# MODUL_GNU-PI_BRIDGE_V100.net
KiCad netlist of a schematic drawn in EAGLE
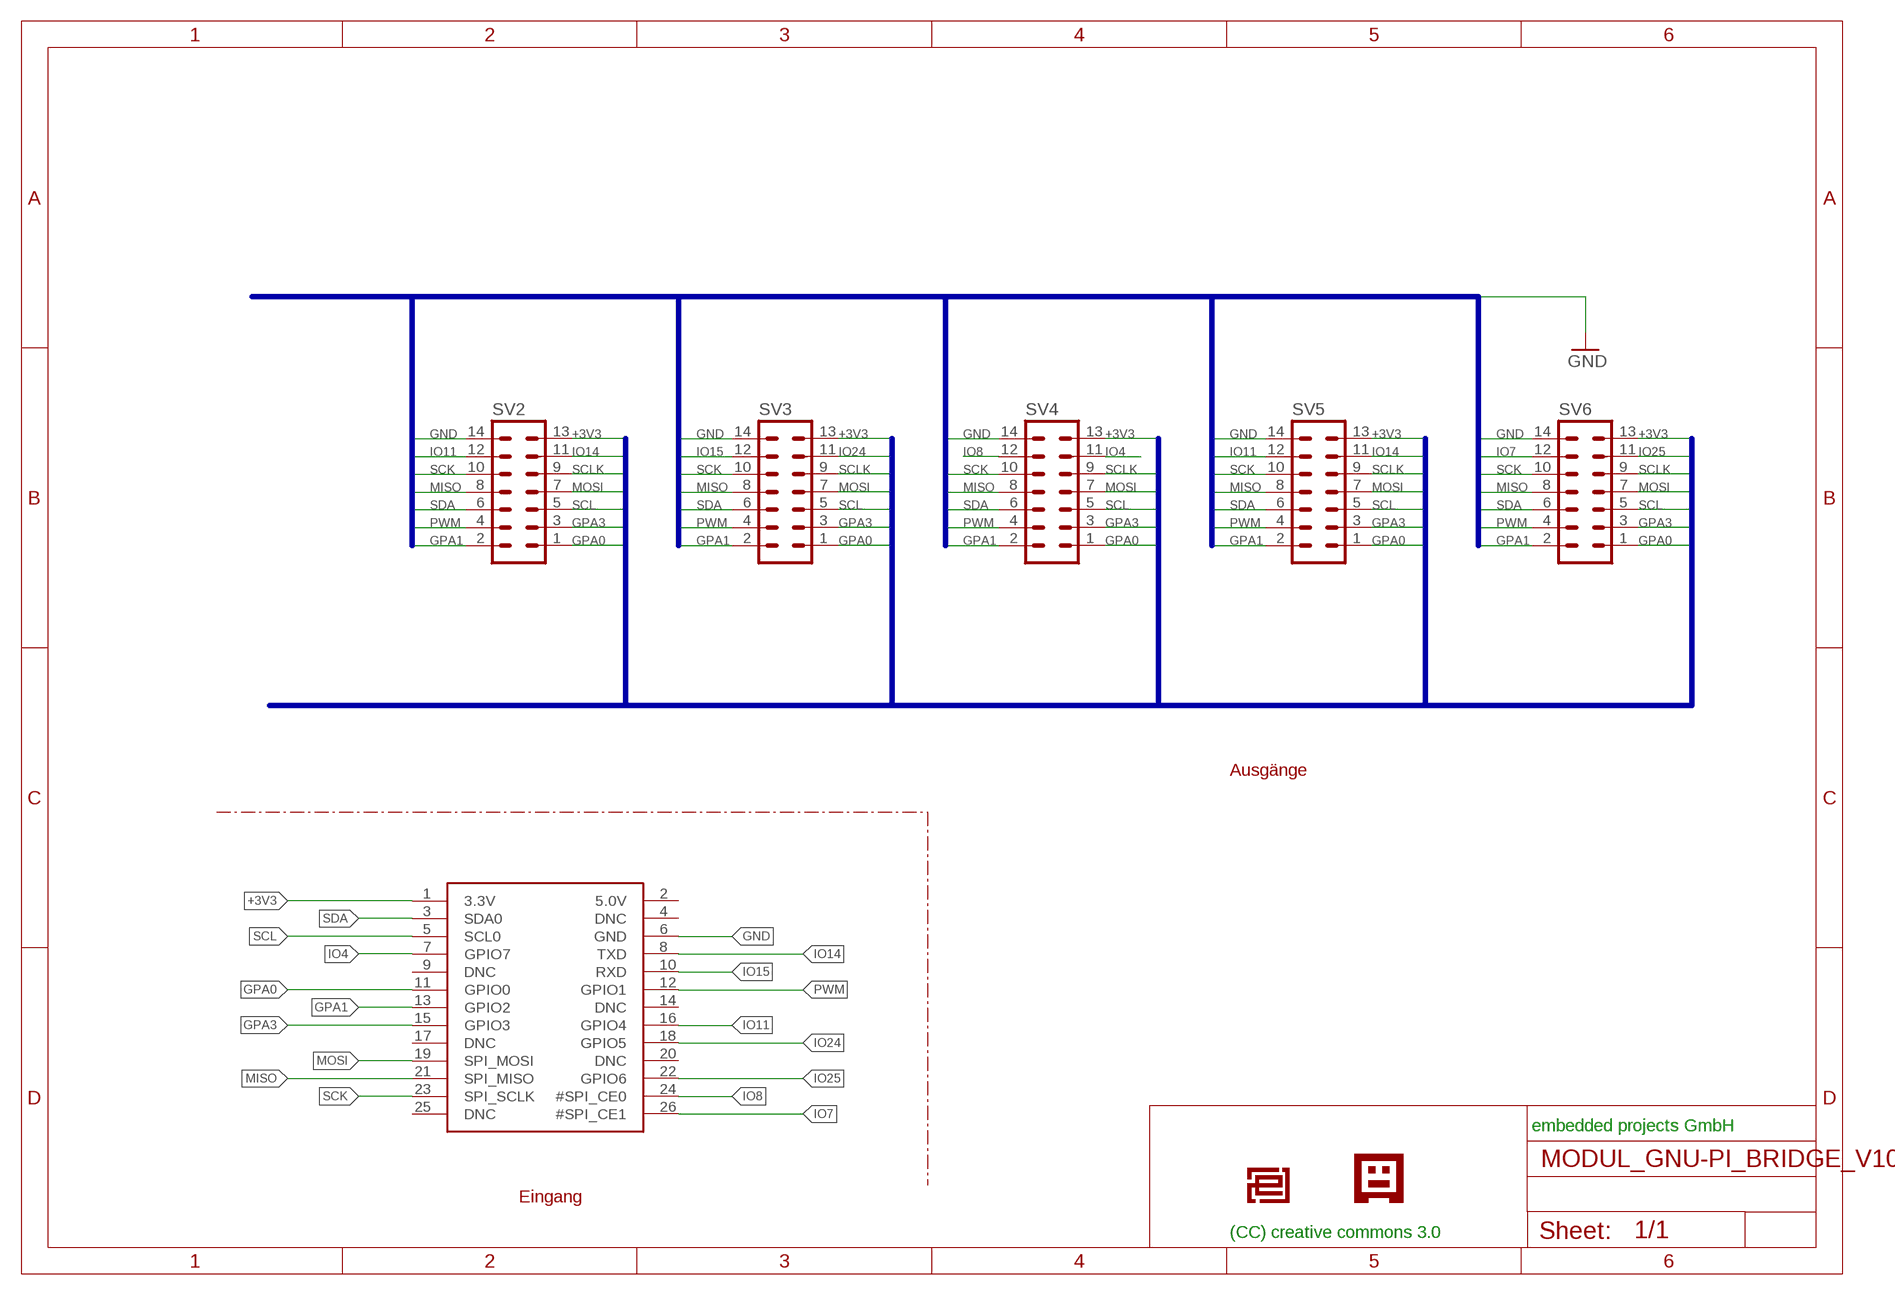
[diagram p0: schematic, sheet 1]

(export (version "E")
  (design (tool "Eeschema 10.0.6"))
  (components
    (comp (ref "SV2")
      (value "ML14")
      (footprint "eagle-import:ML14")
      (libsource (lib "eagle-import") (part "ML14"))
    )
    (comp (ref "SV3")
      (value "ML14")
      (footprint "eagle-import:ML14")
      (libsource (lib "eagle-import") (part "ML14"))
    )
    (comp (ref "SV4")
      (value "ML14")
      (footprint "eagle-import:ML14")
      (libsource (lib "eagle-import") (part "ML14"))
    )
    (comp (ref "SV5")
      (value "ML14")
      (footprint "eagle-import:ML14")
      (libsource (lib "eagle-import") (part "ML14"))
    )
    (comp (ref "SV6")
      (value "ML14")
      (footprint "eagle-import:ML14")
      (libsource (lib "eagle-import") (part "ML14"))
    )
    (comp (ref "U$1")
      (value "RASPBERRYPI_BB")
      (footprint "eagle-import:RASBERRYPI_SHIELD")
      (libsource (lib "eagle-import") (part "RASPBERRYPI_BB"))
    )
    (comp (ref "U$2")
      (value "EPLOGOSIEB")
      (footprint "eagle-import:EPLOGOSIEBDRUCK")
      (libsource (lib "eagle-import") (part "EPLOGOSIEB"))
    )
    (comp (ref "U$4")
      (value "GNUBLINLOGOSIEB")
      (footprint "eagle-import:GNUSIEBDRUCK")
      (libsource (lib "eagle-import") (part "GNUBLINLOGOSIEB"))
    )
  )
  (nets
    (net (code "1") (name "+3V3") (class "Default")
      (node (ref "SV2") (pin "13") (pinfunction "13_13") (pintype "passive"))
      (node (ref "SV3") (pin "13") (pinfunction "13_13") (pintype "passive"))
      (node (ref "SV4") (pin "13") (pinfunction "13_13") (pintype "passive"))
      (node (ref "SV5") (pin "13") (pinfunction "13_13") (pintype "passive"))
      (node (ref "SV6") (pin "13") (pinfunction "13_13") (pintype "passive"))
      (node (ref "U$1") (pin "1") (pinfunction "3.3V_1") (pintype "power_in"))
    )
    (net (code "2") (name "/5.0V") (class "Default")
      (node (ref "U$1") (pin "2") (pinfunction "5.0V_2") (pintype "power_in"))
    )
    (net (code "3") (name "/SCLK") (class "Default")
      (node (ref "SV2") (pin "9") (pinfunction "9_9") (pintype "passive"))
      (node (ref "SV3") (pin "9") (pinfunction "9_9") (pintype "passive"))
      (node (ref "SV4") (pin "9") (pinfunction "9_9") (pintype "passive"))
      (node (ref "SV5") (pin "9") (pinfunction "9_9") (pintype "passive"))
      (node (ref "SV6") (pin "9") (pinfunction "9_9") (pintype "passive"))
    )
    (net (code "4") (name "GND") (class "Default")
      (node (ref "SV2") (pin "14") (pinfunction "14_14") (pintype "passive"))
      (node (ref "SV3") (pin "14") (pinfunction "14_14") (pintype "passive"))
      (node (ref "SV4") (pin "14") (pinfunction "14_14") (pintype "passive"))
      (node (ref "SV5") (pin "14") (pinfunction "14_14") (pintype "passive"))
      (node (ref "SV6") (pin "14") (pinfunction "14_14") (pintype "passive"))
      (node (ref "U$1") (pin "6") (pinfunction "GND_6") (pintype "power_in"))
    )
    (net (code "5") (name "GPA0") (class "Default")
      (node (ref "SV2") (pin "1") (pinfunction "1_1") (pintype "passive"))
      (node (ref "SV3") (pin "1") (pinfunction "1_1") (pintype "passive"))
      (node (ref "SV4") (pin "1") (pinfunction "1_1") (pintype "passive"))
      (node (ref "SV5") (pin "1") (pinfunction "1_1") (pintype "passive"))
      (node (ref "SV6") (pin "1") (pinfunction "1_1") (pintype "passive"))
      (node (ref "U$1") (pin "11") (pinfunction "GPIO0_11") (pintype "bidirectional"))
    )
    (net (code "6") (name "GPA1") (class "Default")
      (node (ref "SV2") (pin "2") (pinfunction "2_2") (pintype "passive"))
      (node (ref "SV3") (pin "2") (pinfunction "2_2") (pintype "passive"))
      (node (ref "SV4") (pin "2") (pinfunction "2_2") (pintype "passive"))
      (node (ref "SV5") (pin "2") (pinfunction "2_2") (pintype "passive"))
      (node (ref "SV6") (pin "2") (pinfunction "2_2") (pintype "passive"))
      (node (ref "U$1") (pin "13") (pinfunction "GPIO2_13") (pintype "bidirectional"))
    )
    (net (code "7") (name "GPA3") (class "Default")
      (node (ref "SV2") (pin "3") (pinfunction "3_3") (pintype "passive"))
      (node (ref "SV3") (pin "3") (pinfunction "3_3") (pintype "passive"))
      (node (ref "SV4") (pin "3") (pinfunction "3_3") (pintype "passive"))
      (node (ref "SV5") (pin "3") (pinfunction "3_3") (pintype "passive"))
      (node (ref "SV6") (pin "3") (pinfunction "3_3") (pintype "passive"))
      (node (ref "U$1") (pin "15") (pinfunction "GPIO3_15") (pintype "bidirectional"))
    )
    (net (code "8") (name "IO4") (class "Default")
      (node (ref "SV4") (pin "11") (pinfunction "11_11") (pintype "passive"))
      (node (ref "U$1") (pin "7") (pinfunction "GPIO7_7") (pintype "bidirectional"))
    )
    (net (code "9") (name "IO7") (class "Default")
      (node (ref "SV6") (pin "12") (pinfunction "12_12") (pintype "passive"))
      (node (ref "U$1") (pin "26") (pinfunction "#SPI_CE1_26") (pintype "output"))
    )
    (net (code "10") (name "IO8") (class "Default")
      (node (ref "SV4") (pin "12") (pinfunction "12_12") (pintype "passive"))
      (node (ref "U$1") (pin "24") (pinfunction "#SPI_CE0_24") (pintype "output"))
    )
    (net (code "11") (name "IO11") (class "Default")
      (node (ref "SV2") (pin "12") (pinfunction "12_12") (pintype "passive"))
      (node (ref "SV5") (pin "12") (pinfunction "12_12") (pintype "passive"))
      (node (ref "U$1") (pin "16") (pinfunction "GPIO4_16") (pintype "bidirectional"))
    )
    (net (code "12") (name "IO14") (class "Default")
      (node (ref "SV2") (pin "11") (pinfunction "11_11") (pintype "passive"))
      (node (ref "SV5") (pin "11") (pinfunction "11_11") (pintype "passive"))
      (node (ref "U$1") (pin "8") (pinfunction "TXD_8") (pintype "output"))
    )
    (net (code "13") (name "IO15") (class "Default")
      (node (ref "SV3") (pin "12") (pinfunction "12_12") (pintype "passive"))
      (node (ref "U$1") (pin "10") (pinfunction "RXD_10") (pintype "input"))
    )
    (net (code "14") (name "IO24") (class "Default")
      (node (ref "SV3") (pin "11") (pinfunction "11_11") (pintype "passive"))
      (node (ref "U$1") (pin "18") (pinfunction "GPIO5_18") (pintype "bidirectional"))
    )
    (net (code "15") (name "IO25") (class "Default")
      (node (ref "SV6") (pin "11") (pinfunction "11_11") (pintype "passive"))
      (node (ref "U$1") (pin "22") (pinfunction "GPIO6_22") (pintype "bidirectional"))
    )
    (net (code "16") (name "MISO") (class "Default")
      (node (ref "SV2") (pin "8") (pinfunction "8_8") (pintype "passive"))
      (node (ref "SV3") (pin "8") (pinfunction "8_8") (pintype "passive"))
      (node (ref "SV4") (pin "8") (pinfunction "8_8") (pintype "passive"))
      (node (ref "SV5") (pin "8") (pinfunction "8_8") (pintype "passive"))
      (node (ref "SV6") (pin "8") (pinfunction "8_8") (pintype "passive"))
      (node (ref "U$1") (pin "21") (pinfunction "SPI_MISO_21") (pintype "input"))
    )
    (net (code "17") (name "MOSI") (class "Default")
      (node (ref "SV2") (pin "7") (pinfunction "7_7") (pintype "passive"))
      (node (ref "SV3") (pin "7") (pinfunction "7_7") (pintype "passive"))
      (node (ref "SV4") (pin "7") (pinfunction "7_7") (pintype "passive"))
      (node (ref "SV5") (pin "7") (pinfunction "7_7") (pintype "passive"))
      (node (ref "SV6") (pin "7") (pinfunction "7_7") (pintype "passive"))
      (node (ref "U$1") (pin "19") (pinfunction "SPI_MOSI_19") (pintype "output"))
    )
    (net (code "18") (name "PWM") (class "Default")
      (node (ref "SV2") (pin "4") (pinfunction "4_4") (pintype "passive"))
      (node (ref "SV3") (pin "4") (pinfunction "4_4") (pintype "passive"))
      (node (ref "SV4") (pin "4") (pinfunction "4_4") (pintype "passive"))
      (node (ref "SV5") (pin "4") (pinfunction "4_4") (pintype "passive"))
      (node (ref "SV6") (pin "4") (pinfunction "4_4") (pintype "passive"))
      (node (ref "U$1") (pin "12") (pinfunction "GPIO1_12") (pintype "bidirectional"))
    )
    (net (code "19") (name "SCK") (class "Default")
      (node (ref "SV2") (pin "10") (pinfunction "10_10") (pintype "passive"))
      (node (ref "SV3") (pin "10") (pinfunction "10_10") (pintype "passive"))
      (node (ref "SV4") (pin "10") (pinfunction "10_10") (pintype "passive"))
      (node (ref "SV5") (pin "10") (pinfunction "10_10") (pintype "passive"))
      (node (ref "SV6") (pin "10") (pinfunction "10_10") (pintype "passive"))
      (node (ref "U$1") (pin "23") (pinfunction "SPI_SCLK_23") (pintype "output"))
    )
    (net (code "20") (name "SCL") (class "Default")
      (node (ref "SV2") (pin "5") (pinfunction "5_5") (pintype "passive"))
      (node (ref "SV3") (pin "5") (pinfunction "5_5") (pintype "passive"))
      (node (ref "SV4") (pin "5") (pinfunction "5_5") (pintype "passive"))
      (node (ref "SV5") (pin "5") (pinfunction "5_5") (pintype "passive"))
      (node (ref "SV6") (pin "5") (pinfunction "5_5") (pintype "passive"))
      (node (ref "U$1") (pin "5") (pinfunction "SCL0_5") (pintype "output"))
    )
    (net (code "21") (name "SDA") (class "Default")
      (node (ref "SV2") (pin "6") (pinfunction "6_6") (pintype "passive"))
      (node (ref "SV3") (pin "6") (pinfunction "6_6") (pintype "passive"))
      (node (ref "SV4") (pin "6") (pinfunction "6_6") (pintype "passive"))
      (node (ref "SV5") (pin "6") (pinfunction "6_6") (pintype "passive"))
      (node (ref "SV6") (pin "6") (pinfunction "6_6") (pintype "passive"))
      (node (ref "U$1") (pin "3") (pinfunction "SDA0_3") (pintype "bidirectional"))
    )
    (net (code "22") (name "unconnected-(U$1-DNC-Pad4)") (class "Default")
      (node (ref "U$1") (pin "4") (pinfunction "DNC_4") (pintype "no_connect"))
    )
    (net (code "23") (name "unconnected-(U$1-DNC-Pad9)") (class "Default")
      (node (ref "U$1") (pin "9") (pinfunction "DNC_9") (pintype "no_connect"))
    )
    (net (code "24") (name "unconnected-(U$1-DNC-Pad14)") (class "Default")
      (node (ref "U$1") (pin "14") (pinfunction "DNC_14") (pintype "no_connect"))
    )
    (net (code "25") (name "unconnected-(U$1-DNC-Pad17)") (class "Default")
      (node (ref "U$1") (pin "17") (pinfunction "DNC_17") (pintype "no_connect"))
    )
    (net (code "26") (name "unconnected-(U$1-DNC-Pad20)") (class "Default")
      (node (ref "U$1") (pin "20") (pinfunction "DNC_20") (pintype "no_connect"))
    )
    (net (code "27") (name "unconnected-(U$1-DNC-Pad25)") (class "Default")
      (node (ref "U$1") (pin "25") (pinfunction "DNC_25") (pintype "no_connect"))
    )
  )
)
